# DIGITAL_INPUT.net
KiCad netlist of a schematic drawn in Altium Designer
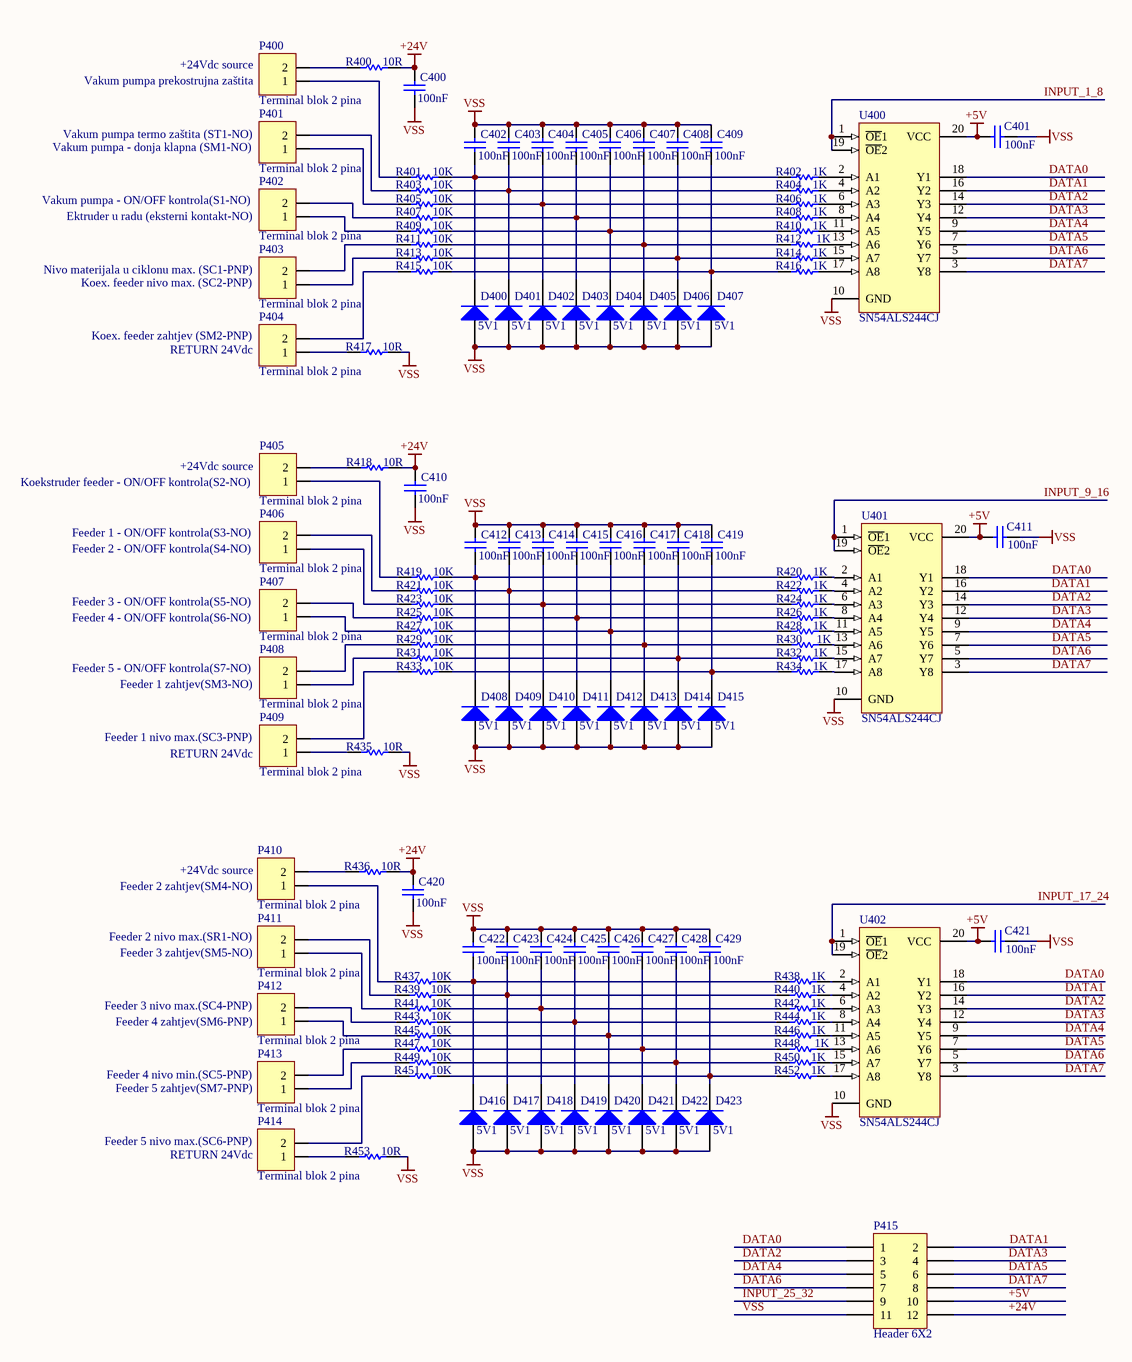
[diagram p0: DIGITAL_INPUT.SchDoc]

(export (version "E")
  (design (tool "Eeschema 10.0.6"))
  (components
    (comp (ref "C400")
      (value "100nF")
      (footprint "1206")
      (description "Ceramic Chip Capacitor - Standard")
      (fields (field (name "PUBLISHER") "Altium Limited"))
      (libsource (lib "KEMET Chip Capacitor") (part "C1206"))
    )
    (comp (ref "C401")
      (value "100nF")
      (footprint "1206")
      (description "Ceramic Chip Capacitor - Standard")
      (fields (field (name "PUBLISHER") "Altium Limited"))
      (libsource (lib "KEMET Chip Capacitor") (part "C1206"))
    )
    (comp (ref "C402")
      (value "100nF")
      (footprint "1206")
      (description "Ceramic Chip Capacitor - Standard")
      (fields (field (name "PUBLISHER") "Altium Limited"))
      (libsource (lib "KEMET Chip Capacitor") (part "C1206"))
    )
    (comp (ref "C403")
      (value "100nF")
      (footprint "1206")
      (description "Ceramic Chip Capacitor - Standard")
      (fields (field (name "PUBLISHER") "Altium Limited"))
      (libsource (lib "KEMET Chip Capacitor") (part "C1206"))
    )
    (comp (ref "C404")
      (value "100nF")
      (footprint "1206")
      (description "Ceramic Chip Capacitor - Standard")
      (fields (field (name "PUBLISHER") "Altium Limited"))
      (libsource (lib "KEMET Chip Capacitor") (part "C1206"))
    )
    (comp (ref "C405")
      (value "100nF")
      (footprint "1206")
      (description "Ceramic Chip Capacitor - Standard")
      (fields (field (name "PUBLISHER") "Altium Limited"))
      (libsource (lib "KEMET Chip Capacitor") (part "C1206"))
    )
    (comp (ref "C406")
      (value "100nF")
      (footprint "1206")
      (description "Ceramic Chip Capacitor - Standard")
      (fields (field (name "PUBLISHER") "Altium Limited"))
      (libsource (lib "KEMET Chip Capacitor") (part "C1206"))
    )
    (comp (ref "C407")
      (value "100nF")
      (footprint "1206")
      (description "Ceramic Chip Capacitor - Standard")
      (fields (field (name "PUBLISHER") "Altium Limited"))
      (libsource (lib "KEMET Chip Capacitor") (part "C1206"))
    )
    (comp (ref "C408")
      (value "100nF")
      (footprint "1206")
      (description "Ceramic Chip Capacitor - Standard")
      (fields (field (name "PUBLISHER") "Altium Limited"))
      (libsource (lib "KEMET Chip Capacitor") (part "C1206"))
    )
    (comp (ref "C409")
      (value "100nF")
      (footprint "1206")
      (description "Ceramic Chip Capacitor - Standard")
      (fields (field (name "PUBLISHER") "Altium Limited"))
      (libsource (lib "KEMET Chip Capacitor") (part "C1206"))
    )
    (comp (ref "C410")
      (value "100nF")
      (footprint "1206")
      (description "Ceramic Chip Capacitor - Standard")
      (fields (field (name "PUBLISHER") "Altium Limited"))
      (libsource (lib "KEMET Chip Capacitor") (part "C1206"))
    )
    (comp (ref "C411")
      (value "100nF")
      (footprint "1206")
      (description "Ceramic Chip Capacitor - Standard")
      (fields (field (name "PUBLISHER") "Altium Limited"))
      (libsource (lib "KEMET Chip Capacitor") (part "C1206"))
    )
    (comp (ref "C412")
      (value "100nF")
      (footprint "1206")
      (description "Ceramic Chip Capacitor - Standard")
      (fields (field (name "PUBLISHER") "Altium Limited"))
      (libsource (lib "KEMET Chip Capacitor") (part "C1206"))
    )
    (comp (ref "C413")
      (value "100nF")
      (footprint "1206")
      (description "Ceramic Chip Capacitor - Standard")
      (fields (field (name "PUBLISHER") "Altium Limited"))
      (libsource (lib "KEMET Chip Capacitor") (part "C1206"))
    )
    (comp (ref "C414")
      (value "100nF")
      (footprint "1206")
      (description "Ceramic Chip Capacitor - Standard")
      (fields (field (name "PUBLISHER") "Altium Limited"))
      (libsource (lib "KEMET Chip Capacitor") (part "C1206"))
    )
    (comp (ref "C415")
      (value "100nF")
      (footprint "1206")
      (description "Ceramic Chip Capacitor - Standard")
      (fields (field (name "PUBLISHER") "Altium Limited"))
      (libsource (lib "KEMET Chip Capacitor") (part "C1206"))
    )
    (comp (ref "C416")
      (value "100nF")
      (footprint "1206")
      (description "Ceramic Chip Capacitor - Standard")
      (fields (field (name "PUBLISHER") "Altium Limited"))
      (libsource (lib "KEMET Chip Capacitor") (part "C1206"))
    )
    (comp (ref "C417")
      (value "100nF")
      (footprint "1206")
      (description "Ceramic Chip Capacitor - Standard")
      (fields (field (name "PUBLISHER") "Altium Limited"))
      (libsource (lib "KEMET Chip Capacitor") (part "C1206"))
    )
    (comp (ref "C418")
      (value "100nF")
      (footprint "1206")
      (description "Ceramic Chip Capacitor - Standard")
      (fields (field (name "PUBLISHER") "Altium Limited"))
      (libsource (lib "KEMET Chip Capacitor") (part "C1206"))
    )
    (comp (ref "C419")
      (value "100nF")
      (footprint "1206")
      (description "Ceramic Chip Capacitor - Standard")
      (fields (field (name "PUBLISHER") "Altium Limited"))
      (libsource (lib "KEMET Chip Capacitor") (part "C1206"))
    )
    (comp (ref "C420")
      (value "100nF")
      (footprint "1206")
      (description "Ceramic Chip Capacitor - Standard")
      (fields (field (name "PUBLISHER") "Altium Limited"))
      (libsource (lib "KEMET Chip Capacitor") (part "C1206"))
    )
    (comp (ref "C421")
      (value "100nF")
      (footprint "1206")
      (description "Ceramic Chip Capacitor - Standard")
      (fields (field (name "PUBLISHER") "Altium Limited"))
      (libsource (lib "KEMET Chip Capacitor") (part "C1206"))
    )
    (comp (ref "C422")
      (value "100nF")
      (footprint "1206")
      (description "Ceramic Chip Capacitor - Standard")
      (fields (field (name "PUBLISHER") "Altium Limited"))
      (libsource (lib "KEMET Chip Capacitor") (part "C1206"))
    )
    (comp (ref "C423")
      (value "100nF")
      (footprint "1206")
      (description "Ceramic Chip Capacitor - Standard")
      (fields (field (name "PUBLISHER") "Altium Limited"))
      (libsource (lib "KEMET Chip Capacitor") (part "C1206"))
    )
    (comp (ref "C424")
      (value "100nF")
      (footprint "1206")
      (description "Ceramic Chip Capacitor - Standard")
      (fields (field (name "PUBLISHER") "Altium Limited"))
      (libsource (lib "KEMET Chip Capacitor") (part "C1206"))
    )
    (comp (ref "C425")
      (value "100nF")
      (footprint "1206")
      (description "Ceramic Chip Capacitor - Standard")
      (fields (field (name "PUBLISHER") "Altium Limited"))
      (libsource (lib "KEMET Chip Capacitor") (part "C1206"))
    )
    (comp (ref "C426")
      (value "100nF")
      (footprint "1206")
      (description "Ceramic Chip Capacitor - Standard")
      (fields (field (name "PUBLISHER") "Altium Limited"))
      (libsource (lib "KEMET Chip Capacitor") (part "C1206"))
    )
    (comp (ref "C427")
      (value "100nF")
      (footprint "1206")
      (description "Ceramic Chip Capacitor - Standard")
      (fields (field (name "PUBLISHER") "Altium Limited"))
      (libsource (lib "KEMET Chip Capacitor") (part "C1206"))
    )
    (comp (ref "C428")
      (value "100nF")
      (footprint "1206")
      (description "Ceramic Chip Capacitor - Standard")
      (fields (field (name "PUBLISHER") "Altium Limited"))
      (libsource (lib "KEMET Chip Capacitor") (part "C1206"))
    )
    (comp (ref "C429")
      (value "100nF")
      (footprint "1206")
      (description "Ceramic Chip Capacitor - Standard")
      (fields (field (name "PUBLISHER") "Altium Limited"))
      (libsource (lib "KEMET Chip Capacitor") (part "C1206"))
    )
    (comp (ref "D400")
      (value "5V1")
      (footprint "SOD80C")
      (description "Voltage Regulator Diode")
      (fields (field (name "PUBLISHER") "Altium Limited"))
      (libsource (lib "Philips Discrete Diode - Switching") (part "BZV85-C5V1"))
    )
    (comp (ref "D401")
      (value "5V1")
      (footprint "SOD80C")
      (description "Voltage Regulator Diode")
      (fields (field (name "PUBLISHER") "Altium Limited"))
      (libsource (lib "Philips Discrete Diode - Switching") (part "BZV85-C5V1"))
    )
    (comp (ref "D402")
      (value "5V1")
      (footprint "SOD80C")
      (description "Voltage Regulator Diode")
      (fields (field (name "PUBLISHER") "Altium Limited"))
      (libsource (lib "Philips Discrete Diode - Switching") (part "BZV85-C5V1"))
    )
    (comp (ref "D403")
      (value "5V1")
      (footprint "SOD80C")
      (description "Voltage Regulator Diode")
      (fields (field (name "PUBLISHER") "Altium Limited"))
      (libsource (lib "Philips Discrete Diode - Switching") (part "BZV85-C5V1"))
    )
    (comp (ref "D404")
      (value "5V1")
      (footprint "SOD80C")
      (description "Voltage Regulator Diode")
      (fields (field (name "PUBLISHER") "Altium Limited"))
      (libsource (lib "Philips Discrete Diode - Switching") (part "BZV85-C5V1"))
    )
    (comp (ref "D405")
      (value "5V1")
      (footprint "SOD80C")
      (description "Voltage Regulator Diode")
      (fields (field (name "PUBLISHER") "Altium Limited"))
      (libsource (lib "Philips Discrete Diode - Switching") (part "BZV85-C5V1"))
    )
    (comp (ref "D406")
      (value "5V1")
      (footprint "SOD80C")
      (description "Voltage Regulator Diode")
      (fields (field (name "PUBLISHER") "Altium Limited"))
      (libsource (lib "Philips Discrete Diode - Switching") (part "BZV85-C5V1"))
    )
    (comp (ref "D407")
      (value "5V1")
      (footprint "SOD80C")
      (description "Voltage Regulator Diode")
      (fields (field (name "PUBLISHER") "Altium Limited"))
      (libsource (lib "Philips Discrete Diode - Switching") (part "BZV85-C5V1"))
    )
    (comp (ref "D408")
      (value "5V1")
      (footprint "SOD80C")
      (description "Voltage Regulator Diode")
      (fields (field (name "PUBLISHER") "Altium Limited"))
      (libsource (lib "Philips Discrete Diode - Switching") (part "BZV85-C5V1"))
    )
    (comp (ref "D409")
      (value "5V1")
      (footprint "SOD80C")
      (description "Voltage Regulator Diode")
      (fields (field (name "PUBLISHER") "Altium Limited"))
      (libsource (lib "Philips Discrete Diode - Switching") (part "BZV85-C5V1"))
    )
    (comp (ref "D410")
      (value "5V1")
      (footprint "SOD80C")
      (description "Voltage Regulator Diode")
      (fields (field (name "PUBLISHER") "Altium Limited"))
      (libsource (lib "Philips Discrete Diode - Switching") (part "BZV85-C5V1"))
    )
    (comp (ref "D411")
      (value "5V1")
      (footprint "SOD80C")
      (description "Voltage Regulator Diode")
      (fields (field (name "PUBLISHER") "Altium Limited"))
      (libsource (lib "Philips Discrete Diode - Switching") (part "BZV85-C5V1"))
    )
    (comp (ref "D412")
      (value "5V1")
      (footprint "SOD80C")
      (description "Voltage Regulator Diode")
      (fields (field (name "PUBLISHER") "Altium Limited"))
      (libsource (lib "Philips Discrete Diode - Switching") (part "BZV85-C5V1"))
    )
    (comp (ref "D413")
      (value "5V1")
      (footprint "SOD80C")
      (description "Voltage Regulator Diode")
      (fields (field (name "PUBLISHER") "Altium Limited"))
      (libsource (lib "Philips Discrete Diode - Switching") (part "BZV85-C5V1"))
    )
    (comp (ref "D414")
      (value "5V1")
      (footprint "SOD80C")
      (description "Voltage Regulator Diode")
      (fields (field (name "PUBLISHER") "Altium Limited"))
      (libsource (lib "Philips Discrete Diode - Switching") (part "BZV85-C5V1"))
    )
    (comp (ref "D415")
      (value "5V1")
      (footprint "SOD80C")
      (description "Voltage Regulator Diode")
      (fields (field (name "PUBLISHER") "Altium Limited"))
      (libsource (lib "Philips Discrete Diode - Switching") (part "BZV85-C5V1"))
    )
    (comp (ref "D416")
      (value "5V1")
      (footprint "SOD80C")
      (description "Voltage Regulator Diode")
      (fields (field (name "PUBLISHER") "Altium Limited"))
      (libsource (lib "Philips Discrete Diode - Switching") (part "BZV85-C5V1"))
    )
    (comp (ref "D417")
      (value "5V1")
      (footprint "SOD80C")
      (description "Voltage Regulator Diode")
      (fields (field (name "PUBLISHER") "Altium Limited"))
      (libsource (lib "Philips Discrete Diode - Switching") (part "BZV85-C5V1"))
    )
    (comp (ref "D418")
      (value "5V1")
      (footprint "SOD80C")
      (description "Voltage Regulator Diode")
      (fields (field (name "PUBLISHER") "Altium Limited"))
      (libsource (lib "Philips Discrete Diode - Switching") (part "BZV85-C5V1"))
    )
    (comp (ref "D419")
      (value "5V1")
      (footprint "SOD80C")
      (description "Voltage Regulator Diode")
      (fields (field (name "PUBLISHER") "Altium Limited"))
      (libsource (lib "Philips Discrete Diode - Switching") (part "BZV85-C5V1"))
    )
    (comp (ref "D420")
      (value "5V1")
      (footprint "SOD80C")
      (description "Voltage Regulator Diode")
      (fields (field (name "PUBLISHER") "Altium Limited"))
      (libsource (lib "Philips Discrete Diode - Switching") (part "BZV85-C5V1"))
    )
    (comp (ref "D421")
      (value "5V1")
      (footprint "SOD80C")
      (description "Voltage Regulator Diode")
      (fields (field (name "PUBLISHER") "Altium Limited"))
      (libsource (lib "Philips Discrete Diode - Switching") (part "BZV85-C5V1"))
    )
    (comp (ref "D422")
      (value "5V1")
      (footprint "SOD80C")
      (description "Voltage Regulator Diode")
      (fields (field (name "PUBLISHER") "Altium Limited"))
      (libsource (lib "Philips Discrete Diode - Switching") (part "BZV85-C5V1"))
    )
    (comp (ref "D423")
      (value "5V1")
      (footprint "SOD80C")
      (description "Voltage Regulator Diode")
      (fields (field (name "PUBLISHER") "Altium Limited"))
      (libsource (lib "Philips Discrete Diode - Switching") (part "BZV85-C5V1"))
    )
    (comp (ref "P400")
      (value "Terminal blok 2 pina")
      (footprint "TERMINAL BLOK 2")
      (description "Terminal blok 2")
      (libsource (lib "") (part "Terminal blok 2 pina_1"))
    )
    (comp (ref "P401")
      (value "Terminal blok 2 pina")
      (footprint "TERMINAL BLOK 2")
      (description "Terminal blok 2")
      (libsource (lib "") (part "Terminal blok 2 pina_1"))
    )
    (comp (ref "P402")
      (value "Terminal blok 2 pina")
      (footprint "TERMINAL BLOK 2")
      (description "Terminal blok 2")
      (libsource (lib "") (part "Terminal blok 2 pina_1"))
    )
    (comp (ref "P403")
      (value "Terminal blok 2 pina")
      (footprint "TERMINAL BLOK 2")
      (description "Terminal blok 2")
      (libsource (lib "TERMINAL_CONNECOR_2") (part "Terminal blok 2 pina"))
    )
    (comp (ref "P404")
      (value "Terminal blok 2 pina")
      (footprint "TERMINAL BLOK 2")
      (description "Terminal blok 2")
      (libsource (lib "TERMINAL_CONNECOR_2") (part "Terminal blok 2 pina"))
    )
    (comp (ref "P405")
      (value "Terminal blok 2 pina")
      (footprint "TERMINAL BLOK 2")
      (description "Terminal blok 2")
      (libsource (lib "TERMINAL_CONNECOR_2") (part "Terminal blok 2 pina"))
    )
    (comp (ref "P406")
      (value "Terminal blok 2 pina")
      (footprint "TERMINAL BLOK 2")
      (description "Terminal blok 2")
      (libsource (lib "TERMINAL_CONNECOR_2") (part "Terminal blok 2 pina"))
    )
    (comp (ref "P407")
      (value "Terminal blok 2 pina")
      (footprint "TERMINAL BLOK 2")
      (description "Terminal blok 2")
      (libsource (lib "TERMINAL_CONNECOR_2") (part "Terminal blok 2 pina"))
    )
    (comp (ref "P408")
      (value "Terminal blok 2 pina")
      (footprint "TERMINAL BLOK 2")
      (description "Terminal blok 2")
      (libsource (lib "TERMINAL_CONNECOR_2") (part "Terminal blok 2 pina"))
    )
    (comp (ref "P409")
      (value "Terminal blok 2 pina")
      (footprint "TERMINAL BLOK 2")
      (description "Terminal blok 2")
      (libsource (lib "TERMINAL_CONNECOR_2") (part "Terminal blok 2 pina"))
    )
    (comp (ref "P410")
      (value "Terminal blok 2 pina")
      (footprint "TERMINAL BLOK 2")
      (description "Terminal blok 2")
      (libsource (lib "") (part "Terminal blok 2 pina_2"))
    )
    (comp (ref "P411")
      (value "Terminal blok 2 pina")
      (footprint "TERMINAL BLOK 2")
      (description "Terminal blok 2")
      (libsource (lib "") (part "Terminal blok 2 pina_2"))
    )
    (comp (ref "P412")
      (value "Terminal blok 2 pina")
      (footprint "TERMINAL BLOK 2")
      (description "Terminal blok 2")
      (libsource (lib "") (part "Terminal blok 2 pina_2"))
    )
    (comp (ref "P413")
      (value "Terminal blok 2 pina")
      (footprint "TERMINAL BLOK 2")
      (description "Terminal blok 2")
      (libsource (lib "") (part "Terminal blok 2 pina_2"))
    )
    (comp (ref "P414")
      (value "Terminal blok 2 pina")
      (footprint "TERMINAL BLOK 2")
      (description "Terminal blok 2")
      (libsource (lib "") (part "Terminal blok 2 pina_2"))
    )
    (comp (ref "P415")
      (value "Header 6X2")
      (footprint "HDR2X6")
      (description "Header, 6-Pin, Dual row")
      (fields (field (name "PUBLISHER") "Altium Limited"))
      (libsource (lib "Miscellaneous Connectors") (part "Header 6X2"))
    )
    (comp (ref "R400")
      (value "10R")
      (footprint "ERA-0805")
      (fields (field (name "PUBLISHER") "Altium Limited"))
      (libsource (lib "Panasonic Resistor") (part "ERA6Y"))
    )
    (comp (ref "R401")
      (value "10K")
      (footprint "ERA-0805")
      (fields (field (name "PUBLISHER") "Altium Limited"))
      (libsource (lib "Panasonic Resistor") (part "ERA6Y"))
    )
    (comp (ref "R402")
      (value "1K")
      (footprint "ERA-0805")
      (fields (field (name "PUBLISHER") "Altium Limited"))
      (libsource (lib "Panasonic Resistor") (part "ERA6Y"))
    )
    (comp (ref "R403")
      (value "10K")
      (footprint "ERA-0805")
      (fields (field (name "PUBLISHER") "Altium Limited"))
      (libsource (lib "Panasonic Resistor") (part "ERA6Y"))
    )
    (comp (ref "R404")
      (value "1K")
      (footprint "ERA-0805")
      (fields (field (name "PUBLISHER") "Altium Limited"))
      (libsource (lib "Panasonic Resistor") (part "ERA6Y"))
    )
    (comp (ref "R405")
      (value "10K")
      (footprint "ERA-0805")
      (fields (field (name "PUBLISHER") "Altium Limited"))
      (libsource (lib "Panasonic Resistor") (part "ERA6Y"))
    )
    (comp (ref "R406")
      (value "1K")
      (footprint "ERA-0805")
      (fields (field (name "PUBLISHER") "Altium Limited"))
      (libsource (lib "Panasonic Resistor") (part "ERA6Y"))
    )
    (comp (ref "R407")
      (value "10K")
      (footprint "ERA-0805")
      (fields (field (name "PUBLISHER") "Altium Limited"))
      (libsource (lib "Panasonic Resistor") (part "ERA6Y"))
    )
    (comp (ref "R408")
      (value "1K")
      (footprint "ERA-0805")
      (fields (field (name "PUBLISHER") "Altium Limited"))
      (libsource (lib "Panasonic Resistor") (part "ERA6Y"))
    )
    (comp (ref "R409")
      (value "10K")
      (footprint "ERA-0805")
      (fields (field (name "PUBLISHER") "Altium Limited"))
      (libsource (lib "Panasonic Resistor") (part "ERA6Y"))
    )
    (comp (ref "R410")
      (value "1K")
      (footprint "ERA-0805")
      (fields (field (name "PUBLISHER") "Altium Limited"))
      (libsource (lib "Panasonic Resistor") (part "ERA6Y"))
    )
    (comp (ref "R411")
      (value "10K")
      (footprint "ERA-0805")
      (fields (field (name "PUBLISHER") "Altium Limited"))
      (libsource (lib "Panasonic Resistor") (part "ERA6Y"))
    )
    (comp (ref "R412")
      (value "1K")
      (footprint "ERA-0805")
      (fields (field (name "PUBLISHER") "Altium Limited"))
      (libsource (lib "Panasonic Resistor") (part "ERA6Y"))
    )
    (comp (ref "R413")
      (value "10K")
      (footprint "ERA-0805")
      (fields (field (name "PUBLISHER") "Altium Limited"))
      (libsource (lib "Panasonic Resistor") (part "ERA6Y"))
    )
    (comp (ref "R414")
      (value "1K")
      (footprint "ERA-0805")
      (fields (field (name "PUBLISHER") "Altium Limited"))
      (libsource (lib "Panasonic Resistor") (part "ERA6Y"))
    )
    (comp (ref "R415")
      (value "10K")
      (footprint "ERA-0805")
      (fields (field (name "PUBLISHER") "Altium Limited"))
      (libsource (lib "Panasonic Resistor") (part "ERA6Y"))
    )
    (comp (ref "R416")
      (value "1K")
      (footprint "ERA-0805")
      (fields (field (name "PUBLISHER") "Altium Limited"))
      (libsource (lib "Panasonic Resistor") (part "ERA6Y"))
    )
    (comp (ref "R417")
      (value "10R")
      (footprint "ERA-0805")
      (fields (field (name "PUBLISHER") "Altium Limited"))
      (libsource (lib "Panasonic Resistor") (part "ERA6Y"))
    )
    (comp (ref "R418")
      (value "10R")
      (footprint "ERA-0805")
      (fields (field (name "PUBLISHER") "Altium Limited"))
      (libsource (lib "Panasonic Resistor") (part "ERA6Y"))
    )
    (comp (ref "R419")
      (value "10K")
      (footprint "ERA-0805")
      (fields (field (name "PUBLISHER") "Altium Limited"))
      (libsource (lib "Panasonic Resistor") (part "ERA6Y"))
    )
    (comp (ref "R420")
      (value "1K")
      (footprint "ERA-0805")
      (fields (field (name "PUBLISHER") "Altium Limited"))
      (libsource (lib "Panasonic Resistor") (part "ERA6Y"))
    )
    (comp (ref "R421")
      (value "10K")
      (footprint "ERA-0805")
      (fields (field (name "PUBLISHER") "Altium Limited"))
      (libsource (lib "Panasonic Resistor") (part "ERA6Y"))
    )
    (comp (ref "R422")
      (value "1K")
      (footprint "ERA-0805")
      (fields (field (name "PUBLISHER") "Altium Limited"))
      (libsource (lib "Panasonic Resistor") (part "ERA6Y"))
    )
    (comp (ref "R423")
      (value "10K")
      (footprint "ERA-0805")
      (fields (field (name "PUBLISHER") "Altium Limited"))
      (libsource (lib "Panasonic Resistor") (part "ERA6Y"))
    )
    (comp (ref "R424")
      (value "1K")
      (footprint "ERA-0805")
      (fields (field (name "PUBLISHER") "Altium Limited"))
      (libsource (lib "Panasonic Resistor") (part "ERA6Y"))
    )
    (comp (ref "R425")
      (value "10K")
      (footprint "ERA-0805")
      (fields (field (name "PUBLISHER") "Altium Limited"))
      (libsource (lib "Panasonic Resistor") (part "ERA6Y"))
    )
    (comp (ref "R426")
      (value "1K")
      (footprint "ERA-0805")
      (fields (field (name "PUBLISHER") "Altium Limited"))
      (libsource (lib "Panasonic Resistor") (part "ERA6Y"))
    )
    (comp (ref "R427")
      (value "10K")
      (footprint "ERA-0805")
      (fields (field (name "PUBLISHER") "Altium Limited"))
      (libsource (lib "Panasonic Resistor") (part "ERA6Y"))
    )
    (comp (ref "R428")
      (value "1K")
      (footprint "ERA-0805")
      (fields (field (name "PUBLISHER") "Altium Limited"))
      (libsource (lib "Panasonic Resistor") (part "ERA6Y"))
    )
    (comp (ref "R429")
      (value "10K")
      (footprint "ERA-0805")
      (fields (field (name "PUBLISHER") "Altium Limited"))
      (libsource (lib "Panasonic Resistor") (part "ERA6Y"))
    )
    (comp (ref "R430")
      (value "1K")
      (footprint "ERA-0805")
      (fields (field (name "PUBLISHER") "Altium Limited"))
      (libsource (lib "Panasonic Resistor") (part "ERA6Y"))
    )
    (comp (ref "R431")
      (value "10K")
      (footprint "ERA-0805")
      (fields (field (name "PUBLISHER") "Altium Limited"))
      (libsource (lib "Panasonic Resistor") (part "ERA6Y"))
    )
    (comp (ref "R432")
      (value "1K")
      (footprint "ERA-0805")
      (fields (field (name "PUBLISHER") "Altium Limited"))
      (libsource (lib "Panasonic Resistor") (part "ERA6Y"))
    )
    (comp (ref "R433")
      (value "10K")
      (footprint "ERA-0805")
      (fields (field (name "PUBLISHER") "Altium Limited"))
      (libsource (lib "Panasonic Resistor") (part "ERA6Y"))
    )
    (comp (ref "R434")
      (value "1K")
      (footprint "ERA-0805")
      (fields (field (name "PUBLISHER") "Altium Limited"))
      (libsource (lib "Panasonic Resistor") (part "ERA6Y"))
    )
    (comp (ref "R435")
      (value "10R")
      (footprint "ERA-0805")
      (fields (field (name "PUBLISHER") "Altium Limited"))
      (libsource (lib "Panasonic Resistor") (part "ERA6Y"))
    )
    (comp (ref "R436")
      (value "10R")
      (footprint "ERA-0805")
      (fields (field (name "PUBLISHER") "Altium Limited"))
      (libsource (lib "Panasonic Resistor") (part "ERA6Y"))
    )
    (comp (ref "R437")
      (value "10K")
      (footprint "ERA-0805")
      (fields (field (name "PUBLISHER") "Altium Limited"))
      (libsource (lib "Panasonic Resistor") (part "ERA6Y"))
    )
    (comp (ref "R438")
      (value "1K")
      (footprint "ERA-0805")
      (fields (field (name "PUBLISHER") "Altium Limited"))
      (libsource (lib "Panasonic Resistor") (part "ERA6Y"))
    )
    (comp (ref "R439")
      (value "10K")
      (footprint "ERA-0805")
      (fields (field (name "PUBLISHER") "Altium Limited"))
      (libsource (lib "Panasonic Resistor") (part "ERA6Y"))
    )
    (comp (ref "R440")
      (value "1K")
      (footprint "ERA-0805")
      (fields (field (name "PUBLISHER") "Altium Limited"))
      (libsource (lib "Panasonic Resistor") (part "ERA6Y"))
    )
    (comp (ref "R441")
      (value "10K")
      (footprint "ERA-0805")
      (fields (field (name "PUBLISHER") "Altium Limited"))
      (libsource (lib "Panasonic Resistor") (part "ERA6Y"))
    )
    (comp (ref "R442")
      (value "1K")
      (footprint "ERA-0805")
      (fields (field (name "PUBLISHER") "Altium Limited"))
      (libsource (lib "Panasonic Resistor") (part "ERA6Y"))
    )
    (comp (ref "R443")
      (value "10K")
      (footprint "ERA-0805")
      (fields (field (name "PUBLISHER") "Altium Limited"))
      (libsource (lib "Panasonic Resistor") (part "ERA6Y"))
    )
    (comp (ref "R444")
      (value "1K")
      (footprint "ERA-0805")
      (fields (field (name "PUBLISHER") "Altium Limited"))
      (libsource (lib "Panasonic Resistor") (part "ERA6Y"))
    )
    (comp (ref "R445")
      (value "10K")
      (footprint "ERA-0805")
      (fields (field (name "PUBLISHER") "Altium Limited"))
      (libsource (lib "Panasonic Resistor") (part "ERA6Y"))
    )
    (comp (ref "R446")
      (value "1K")
      (footprint "ERA-0805")
      (fields (field (name "PUBLISHER") "Altium Limited"))
      (libsource (lib "Panasonic Resistor") (part "ERA6Y"))
    )
    (comp (ref "R447")
      (value "10K")
      (footprint "ERA-0805")
      (fields (field (name "PUBLISHER") "Altium Limited"))
      (libsource (lib "Panasonic Resistor") (part "ERA6Y"))
    )
    (comp (ref "R448")
      (value "1K")
      (footprint "ERA-0805")
      (fields (field (name "PUBLISHER") "Altium Limited"))
      (libsource (lib "Panasonic Resistor") (part "ERA6Y"))
    )
    (comp (ref "R449")
      (value "10K")
      (footprint "ERA-0805")
      (fields (field (name "PUBLISHER") "Altium Limited"))
      (libsource (lib "Panasonic Resistor") (part "ERA6Y"))
    )
    (comp (ref "R450")
      (value "1K")
      (footprint "ERA-0805")
      (fields (field (name "PUBLISHER") "Altium Limited"))
      (libsource (lib "Panasonic Resistor") (part "ERA6Y"))
    )
    (comp (ref "R451")
      (value "10K")
      (footprint "ERA-0805")
      (fields (field (name "PUBLISHER") "Altium Limited"))
      (libsource (lib "Panasonic Resistor") (part "ERA6Y"))
    )
    (comp (ref "R452")
      (value "1K")
      (footprint "ERA-0805")
      (fields (field (name "PUBLISHER") "Altium Limited"))
      (libsource (lib "Panasonic Resistor") (part "ERA6Y"))
    )
    (comp (ref "R453")
      (value "10R")
      (footprint "ERA-0805")
      (fields (field (name "PUBLISHER") "Altium Limited"))
      (libsource (lib "Panasonic Resistor") (part "ERA6Y"))
    )
    (comp (ref "U400")
      (value "SN54ALS244CJ")
      (footprint "J020")
      (description "Octal Buffer/Driver with 3-State Outputs")
      (fields (field (name "PUBLISHER") "Altium Limited"))
      (libsource (lib "TI Logic Buffer Line Driver") (part "SN54ALS244CJ"))
    )
    (comp (ref "U401")
      (value "SN54ALS244CJ")
      (footprint "J020")
      (description "Octal Buffer/Driver with 3-State Outputs")
      (fields (field (name "PUBLISHER") "Altium Limited"))
      (libsource (lib "TI Logic Buffer Line Driver") (part "SN54ALS244CJ"))
    )
    (comp (ref "U402")
      (value "SN54ALS244CJ")
      (footprint "J020")
      (description "Octal Buffer/Driver with 3-State Outputs")
      (fields (field (name "PUBLISHER") "Altium Limited"))
      (libsource (lib "TI Logic Buffer Line Driver") (part "SN54ALS244CJ"))
    )
  )
  (nets
    (net (code "1") (name "+5V") (class "Default")
      (node (ref "C401") (pin "1") (pinfunction "1_1") (pintype "passive"))
      (node (ref "C411") (pin "1") (pinfunction "1_1") (pintype "passive"))
      (node (ref "C421") (pin "1") (pinfunction "1_1") (pintype "passive"))
      (node (ref "P415") (pin "10") (pinfunction "10_10") (pintype "passive"))
      (node (ref "U400") (pin "20") (pinfunction "VCC_20") (pintype "power_in"))
      (node (ref "U401") (pin "20") (pinfunction "VCC_20") (pintype "power_in"))
      (node (ref "U402") (pin "20") (pinfunction "VCC_20") (pintype "power_in"))
    )
    (net (code "2") (name "+24V") (class "Default")
      (node (ref "C400") (pin "2") (pinfunction "2_2") (pintype "passive"))
      (node (ref "C410") (pin "2") (pinfunction "2_2") (pintype "passive"))
      (node (ref "C420") (pin "2") (pinfunction "2_2") (pintype "passive"))
      (node (ref "P415") (pin "12") (pinfunction "12_12") (pintype "passive"))
      (node (ref "R400") (pin "2") (pinfunction "2_2") (pintype "passive"))
      (node (ref "R418") (pin "2") (pinfunction "2_2") (pintype "passive"))
      (node (ref "R436") (pin "2") (pinfunction "2_2") (pintype "passive"))
    )
    (net (code "3") (name "/DATA0") (class "Default")
      (node (ref "P415") (pin "1") (pinfunction "1_1") (pintype "passive"))
      (node (ref "U400") (pin "18") (pinfunction "Y1_18") (pintype "tri_state"))
      (node (ref "U401") (pin "18") (pinfunction "Y1_18") (pintype "tri_state"))
      (node (ref "U402") (pin "18") (pinfunction "Y1_18") (pintype "tri_state"))
    )
    (net (code "4") (name "/DATA1") (class "Default")
      (node (ref "P415") (pin "2") (pinfunction "2_2") (pintype "passive"))
      (node (ref "U400") (pin "16") (pinfunction "Y2_16") (pintype "tri_state"))
      (node (ref "U401") (pin "16") (pinfunction "Y2_16") (pintype "tri_state"))
      (node (ref "U402") (pin "16") (pinfunction "Y2_16") (pintype "tri_state"))
    )
    (net (code "5") (name "/DATA2") (class "Default")
      (node (ref "P415") (pin "3") (pinfunction "3_3") (pintype "passive"))
      (node (ref "U400") (pin "14") (pinfunction "Y3_14") (pintype "tri_state"))
      (node (ref "U401") (pin "14") (pinfunction "Y3_14") (pintype "tri_state"))
      (node (ref "U402") (pin "14") (pinfunction "Y3_14") (pintype "tri_state"))
    )
    (net (code "6") (name "/DATA3") (class "Default")
      (node (ref "P415") (pin "4") (pinfunction "4_4") (pintype "passive"))
      (node (ref "U400") (pin "12") (pinfunction "Y4_12") (pintype "tri_state"))
      (node (ref "U401") (pin "12") (pinfunction "Y4_12") (pintype "tri_state"))
      (node (ref "U402") (pin "12") (pinfunction "Y4_12") (pintype "tri_state"))
    )
    (net (code "7") (name "/DATA4") (class "Default")
      (node (ref "P415") (pin "5") (pinfunction "5_5") (pintype "passive"))
      (node (ref "U400") (pin "9") (pinfunction "Y5_9") (pintype "tri_state"))
      (node (ref "U401") (pin "9") (pinfunction "Y5_9") (pintype "tri_state"))
      (node (ref "U402") (pin "9") (pinfunction "Y5_9") (pintype "tri_state"))
    )
    (net (code "8") (name "/DATA5") (class "Default")
      (node (ref "P415") (pin "6") (pinfunction "6_6") (pintype "passive"))
      (node (ref "U400") (pin "7") (pinfunction "Y6_7") (pintype "tri_state"))
      (node (ref "U401") (pin "7") (pinfunction "Y6_7") (pintype "tri_state"))
      (node (ref "U402") (pin "7") (pinfunction "Y6_7") (pintype "tri_state"))
    )
    (net (code "9") (name "/DATA6") (class "Default")
      (node (ref "P415") (pin "7") (pinfunction "7_7") (pintype "passive"))
      (node (ref "U400") (pin "5") (pinfunction "Y7_5") (pintype "tri_state"))
      (node (ref "U401") (pin "5") (pinfunction "Y7_5") (pintype "tri_state"))
      (node (ref "U402") (pin "5") (pinfunction "Y7_5") (pintype "tri_state"))
    )
    (net (code "10") (name "/DATA7") (class "Default")
      (node (ref "P415") (pin "8") (pinfunction "8_8") (pintype "passive"))
      (node (ref "U400") (pin "3") (pinfunction "Y8_3") (pintype "tri_state"))
      (node (ref "U401") (pin "3") (pinfunction "Y8_3") (pintype "tri_state"))
      (node (ref "U402") (pin "3") (pinfunction "Y8_3") (pintype "tri_state"))
    )
    (net (code "11") (name "/INPUT_1_8") (class "Default")
      (node (ref "U400") (pin "1") (pinfunction "~{OE}1_1") (pintype "input"))
      (node (ref "U400") (pin "19") (pinfunction "~{OE}2_19") (pintype "input"))
    )
    (net (code "12") (name "/INPUT_9_16") (class "Default")
      (node (ref "U401") (pin "1") (pinfunction "~{OE}1_1") (pintype "input"))
      (node (ref "U401") (pin "19") (pinfunction "~{OE}2_19") (pintype "input"))
    )
    (net (code "13") (name "/INPUT_17_24") (class "Default")
      (node (ref "U402") (pin "1") (pinfunction "~{OE}1_1") (pintype "input"))
      (node (ref "U402") (pin "19") (pinfunction "~{OE}2_19") (pintype "input"))
    )
    (net (code "14") (name "/INPUT_25_32") (class "Default")
      (node (ref "P415") (pin "9") (pinfunction "9_9") (pintype "passive"))
    )
    (net (code "15") (name "Net-(D400-K)") (class "Default")
      (node (ref "C402") (pin "1") (pinfunction "1_1") (pintype "passive"))
      (node (ref "D400") (pin "2") (pinfunction "K_2") (pintype "passive"))
      (node (ref "R401") (pin "2") (pinfunction "2_2") (pintype "passive"))
      (node (ref "R402") (pin "1") (pinfunction "1_1") (pintype "passive"))
    )
    (net (code "16") (name "Net-(D401-K)") (class "Default")
      (node (ref "C403") (pin "1") (pinfunction "1_1") (pintype "passive"))
      (node (ref "D401") (pin "2") (pinfunction "K_2") (pintype "passive"))
      (node (ref "R403") (pin "2") (pinfunction "2_2") (pintype "passive"))
      (node (ref "R404") (pin "1") (pinfunction "1_1") (pintype "passive"))
    )
    (net (code "17") (name "Net-(D402-K)") (class "Default")
      (node (ref "C404") (pin "1") (pinfunction "1_1") (pintype "passive"))
      (node (ref "D402") (pin "2") (pinfunction "K_2") (pintype "passive"))
      (node (ref "R405") (pin "2") (pinfunction "2_2") (pintype "passive"))
      (node (ref "R406") (pin "1") (pinfunction "1_1") (pintype "passive"))
    )
    (net (code "18") (name "Net-(D403-K)") (class "Default")
      (node (ref "C405") (pin "1") (pinfunction "1_1") (pintype "passive"))
      (node (ref "D403") (pin "2") (pinfunction "K_2") (pintype "passive"))
      (node (ref "R407") (pin "2") (pinfunction "2_2") (pintype "passive"))
      (node (ref "R408") (pin "1") (pinfunction "1_1") (pintype "passive"))
    )
    (net (code "19") (name "Net-(D404-K)") (class "Default")
      (node (ref "C406") (pin "1") (pinfunction "1_1") (pintype "passive"))
      (node (ref "D404") (pin "2") (pinfunction "K_2") (pintype "passive"))
      (node (ref "R409") (pin "2") (pinfunction "2_2") (pintype "passive"))
      (node (ref "R410") (pin "1") (pinfunction "1_1") (pintype "passive"))
    )
    (net (code "20") (name "Net-(D405-K)") (class "Default")
      (node (ref "C407") (pin "1") (pinfunction "1_1") (pintype "passive"))
      (node (ref "D405") (pin "2") (pinfunction "K_2") (pintype "passive"))
      (node (ref "R411") (pin "2") (pinfunction "2_2") (pintype "passive"))
      (node (ref "R412") (pin "1") (pinfunction "1_1") (pintype "passive"))
    )
    (net (code "21") (name "Net-(D406-K)") (class "Default")
      (node (ref "C408") (pin "1") (pinfunction "1_1") (pintype "passive"))
      (node (ref "D406") (pin "2") (pinfunction "K_2") (pintype "passive"))
      (node (ref "R413") (pin "2") (pinfunction "2_2") (pintype "passive"))
      (node (ref "R414") (pin "1") (pinfunction "1_1") (pintype "passive"))
    )
    (net (code "22") (name "Net-(D407-K)") (class "Default")
      (node (ref "C409") (pin "1") (pinfunction "1_1") (pintype "passive"))
      (node (ref "D407") (pin "2") (pinfunction "K_2") (pintype "passive"))
      (node (ref "R415") (pin "2") (pinfunction "2_2") (pintype "passive"))
      (node (ref "R416") (pin "1") (pinfunction "1_1") (pintype "passive"))
    )
    (net (code "23") (name "Net-(D408-K)") (class "Default")
      (node (ref "C412") (pin "1") (pinfunction "1_1") (pintype "passive"))
      (node (ref "D408") (pin "2") (pinfunction "K_2") (pintype "passive"))
      (node (ref "R419") (pin "2") (pinfunction "2_2") (pintype "passive"))
      (node (ref "R420") (pin "1") (pinfunction "1_1") (pintype "passive"))
    )
    (net (code "24") (name "Net-(D409-K)") (class "Default")
      (node (ref "C413") (pin "1") (pinfunction "1_1") (pintype "passive"))
      (node (ref "D409") (pin "2") (pinfunction "K_2") (pintype "passive"))
      (node (ref "R421") (pin "2") (pinfunction "2_2") (pintype "passive"))
      (node (ref "R422") (pin "1") (pinfunction "1_1") (pintype "passive"))
    )
    (net (code "25") (name "Net-(D410-K)") (class "Default")
      (node (ref "C414") (pin "1") (pinfunction "1_1") (pintype "passive"))
      (node (ref "D410") (pin "2") (pinfunction "K_2") (pintype "passive"))
      (node (ref "R423") (pin "2") (pinfunction "2_2") (pintype "passive"))
      (node (ref "R424") (pin "1") (pinfunction "1_1") (pintype "passive"))
    )
    (net (code "26") (name "Net-(D411-K)") (class "Default")
      (node (ref "C415") (pin "1") (pinfunction "1_1") (pintype "passive"))
      (node (ref "D411") (pin "2") (pinfunction "K_2") (pintype "passive"))
      (node (ref "R425") (pin "2") (pinfunction "2_2") (pintype "passive"))
      (node (ref "R426") (pin "1") (pinfunction "1_1") (pintype "passive"))
    )
    (net (code "27") (name "Net-(D412-K)") (class "Default")
      (node (ref "C416") (pin "1") (pinfunction "1_1") (pintype "passive"))
      (node (ref "D412") (pin "2") (pinfunction "K_2") (pintype "passive"))
      (node (ref "R427") (pin "2") (pinfunction "2_2") (pintype "passive"))
      (node (ref "R428") (pin "1") (pinfunction "1_1") (pintype "passive"))
    )
    (net (code "28") (name "Net-(D413-K)") (class "Default")
      (node (ref "C417") (pin "1") (pinfunction "1_1") (pintype "passive"))
      (node (ref "D413") (pin "2") (pinfunction "K_2") (pintype "passive"))
      (node (ref "R429") (pin "2") (pinfunction "2_2") (pintype "passive"))
      (node (ref "R430") (pin "1") (pinfunction "1_1") (pintype "passive"))
    )
    (net (code "29") (name "Net-(D414-K)") (class "Default")
      (node (ref "C418") (pin "1") (pinfunction "1_1") (pintype "passive"))
      (node (ref "D414") (pin "2") (pinfunction "K_2") (pintype "passive"))
      (node (ref "R431") (pin "2") (pinfunction "2_2") (pintype "passive"))
      (node (ref "R432") (pin "1") (pinfunction "1_1") (pintype "passive"))
    )
    (net (code "30") (name "Net-(D415-K)") (class "Default")
      (node (ref "C419") (pin "1") (pinfunction "1_1") (pintype "passive"))
      (node (ref "D415") (pin "2") (pinfunction "K_2") (pintype "passive"))
      (node (ref "R433") (pin "2") (pinfunction "2_2") (pintype "passive"))
      (node (ref "R434") (pin "1") (pinfunction "1_1") (pintype "passive"))
    )
    (net (code "31") (name "Net-(D416-K)") (class "Default")
      (node (ref "C422") (pin "1") (pinfunction "1_1") (pintype "passive"))
      (node (ref "D416") (pin "2") (pinfunction "K_2") (pintype "passive"))
      (node (ref "R437") (pin "2") (pinfunction "2_2") (pintype "passive"))
      (node (ref "R438") (pin "1") (pinfunction "1_1") (pintype "passive"))
    )
    (net (code "32") (name "Net-(D417-K)") (class "Default")
      (node (ref "C423") (pin "1") (pinfunction "1_1") (pintype "passive"))
      (node (ref "D417") (pin "2") (pinfunction "K_2") (pintype "passive"))
      (node (ref "R439") (pin "2") (pinfunction "2_2") (pintype "passive"))
      (node (ref "R440") (pin "1") (pinfunction "1_1") (pintype "passive"))
    )
    (net (code "33") (name "Net-(D418-K)") (class "Default")
      (node (ref "C424") (pin "1") (pinfunction "1_1") (pintype "passive"))
      (node (ref "D418") (pin "2") (pinfunction "K_2") (pintype "passive"))
      (node (ref "R441") (pin "2") (pinfunction "2_2") (pintype "passive"))
      (node (ref "R442") (pin "1") (pinfunction "1_1") (pintype "passive"))
    )
    (net (code "34") (name "Net-(D419-K)") (class "Default")
      (node (ref "C425") (pin "1") (pinfunction "1_1") (pintype "passive"))
      (node (ref "D419") (pin "2") (pinfunction "K_2") (pintype "passive"))
      (node (ref "R443") (pin "2") (pinfunction "2_2") (pintype "passive"))
      (node (ref "R444") (pin "1") (pinfunction "1_1") (pintype "passive"))
    )
    (net (code "35") (name "Net-(D420-K)") (class "Default")
      (node (ref "C426") (pin "1") (pinfunction "1_1") (pintype "passive"))
      (node (ref "D420") (pin "2") (pinfunction "K_2") (pintype "passive"))
      (node (ref "R445") (pin "2") (pinfunction "2_2") (pintype "passive"))
      (node (ref "R446") (pin "1") (pinfunction "1_1") (pintype "passive"))
    )
    (net (code "36") (name "Net-(D421-K)") (class "Default")
      (node (ref "C427") (pin "1") (pinfunction "1_1") (pintype "passive"))
      (node (ref "D421") (pin "2") (pinfunction "K_2") (pintype "passive"))
      (node (ref "R447") (pin "2") (pinfunction "2_2") (pintype "passive"))
      (node (ref "R448") (pin "1") (pinfunction "1_1") (pintype "passive"))
    )
    (net (code "37") (name "Net-(D422-K)") (class "Default")
      (node (ref "C428") (pin "1") (pinfunction "1_1") (pintype "passive"))
      (node (ref "D422") (pin "2") (pinfunction "K_2") (pintype "passive"))
      (node (ref "R449") (pin "2") (pinfunction "2_2") (pintype "passive"))
      (node (ref "R450") (pin "1") (pinfunction "1_1") (pintype "passive"))
    )
    (net (code "38") (name "Net-(D423-K)") (class "Default")
      (node (ref "C429") (pin "1") (pinfunction "1_1") (pintype "passive"))
      (node (ref "D423") (pin "2") (pinfunction "K_2") (pintype "passive"))
      (node (ref "R451") (pin "2") (pinfunction "2_2") (pintype "passive"))
      (node (ref "R452") (pin "1") (pinfunction "1_1") (pintype "passive"))
    )
    (net (code "39") (name "Net-(P400-Pad1)") (class "Default")
      (node (ref "P400") (pin "1") (pinfunction "1_1") (pintype "passive"))
      (node (ref "R401") (pin "1") (pinfunction "1_1") (pintype "passive"))
    )
    (net (code "40") (name "Net-(P400-Pad2)") (class "Default")
      (node (ref "P400") (pin "2") (pinfunction "2_2") (pintype "passive"))
      (node (ref "R400") (pin "1") (pinfunction "1_1") (pintype "passive"))
    )
    (net (code "41") (name "Net-(P401-Pad1)") (class "Default")
      (node (ref "P401") (pin "1") (pinfunction "1_1") (pintype "passive"))
      (node (ref "R405") (pin "1") (pinfunction "1_1") (pintype "passive"))
    )
    (net (code "42") (name "Net-(P401-Pad2)") (class "Default")
      (node (ref "P401") (pin "2") (pinfunction "2_2") (pintype "passive"))
      (node (ref "R403") (pin "1") (pinfunction "1_1") (pintype "passive"))
    )
    (net (code "43") (name "Net-(P402-Pad1)") (class "Default")
      (node (ref "P402") (pin "1") (pinfunction "1_1") (pintype "passive"))
      (node (ref "R409") (pin "1") (pinfunction "1_1") (pintype "passive"))
    )
    (net (code "44") (name "Net-(P402-Pad2)") (class "Default")
      (node (ref "P402") (pin "2") (pinfunction "2_2") (pintype "passive"))
      (node (ref "R407") (pin "1") (pinfunction "1_1") (pintype "passive"))
    )
    (net (code "45") (name "Net-(P403-Pad1)") (class "Default")
      (node (ref "P403") (pin "1") (pinfunction "1_1") (pintype "passive"))
      (node (ref "R413") (pin "1") (pinfunction "1_1") (pintype "passive"))
    )
    (net (code "46") (name "Net-(P403-Pad2)") (class "Default")
      (node (ref "P403") (pin "2") (pinfunction "2_2") (pintype "passive"))
      (node (ref "R411") (pin "1") (pinfunction "1_1") (pintype "passive"))
    )
    (net (code "47") (name "Net-(P404-Pad1)") (class "Default")
      (node (ref "P404") (pin "1") (pinfunction "1_1") (pintype "passive"))
      (node (ref "R417") (pin "1") (pinfunction "1_1") (pintype "passive"))
    )
    (net (code "48") (name "Net-(P404-Pad2)") (class "Default")
      (node (ref "P404") (pin "2") (pinfunction "2_2") (pintype "passive"))
      (node (ref "R415") (pin "1") (pinfunction "1_1") (pintype "passive"))
    )
    (net (code "49") (name "Net-(P405-Pad1)") (class "Default")
      (node (ref "P405") (pin "1") (pinfunction "1_1") (pintype "passive"))
      (node (ref "R419") (pin "1") (pinfunction "1_1") (pintype "passive"))
    )
    (net (code "50") (name "Net-(P405-Pad2)") (class "Default")
      (node (ref "P405") (pin "2") (pinfunction "2_2") (pintype "passive"))
      (node (ref "R418") (pin "1") (pinfunction "1_1") (pintype "passive"))
    )
    (net (code "51") (name "Net-(P406-Pad1)") (class "Default")
      (node (ref "P406") (pin "1") (pinfunction "1_1") (pintype "passive"))
      (node (ref "R423") (pin "1") (pinfunction "1_1") (pintype "passive"))
    )
    (net (code "52") (name "Net-(P406-Pad2)") (class "Default")
      (node (ref "P406") (pin "2") (pinfunction "2_2") (pintype "passive"))
      (node (ref "R421") (pin "1") (pinfunction "1_1") (pintype "passive"))
    )
    (net (code "53") (name "Net-(P407-Pad1)") (class "Default")
      (node (ref "P407") (pin "1") (pinfunction "1_1") (pintype "passive"))
      (node (ref "R427") (pin "1") (pinfunction "1_1") (pintype "passive"))
    )
    (net (code "54") (name "Net-(P407-Pad2)") (class "Default")
      (node (ref "P407") (pin "2") (pinfunction "2_2") (pintype "passive"))
      (node (ref "R425") (pin "1") (pinfunction "1_1") (pintype "passive"))
    )
    (net (code "55") (name "Net-(P408-Pad1)") (class "Default")
      (node (ref "P408") (pin "1") (pinfunction "1_1") (pintype "passive"))
      (node (ref "R431") (pin "1") (pinfunction "1_1") (pintype "passive"))
    )
    (net (code "56") (name "Net-(P408-Pad2)") (class "Default")
      (node (ref "P408") (pin "2") (pinfunction "2_2") (pintype "passive"))
      (node (ref "R429") (pin "1") (pinfunction "1_1") (pintype "passive"))
    )
    (net (code "57") (name "Net-(P409-Pad1)") (class "Default")
      (node (ref "P409") (pin "1") (pinfunction "1_1") (pintype "passive"))
      (node (ref "R435") (pin "1") (pinfunction "1_1") (pintype "passive"))
    )
    (net (code "58") (name "Net-(P409-Pad2)") (class "Default")
      (node (ref "P409") (pin "2") (pinfunction "2_2") (pintype "passive"))
      (node (ref "R433") (pin "1") (pinfunction "1_1") (pintype "passive"))
    )
    (net (code "59") (name "Net-(P410-Pad1)") (class "Default")
      (node (ref "P410") (pin "1") (pinfunction "1_1") (pintype "passive"))
      (node (ref "R437") (pin "1") (pinfunction "1_1") (pintype "passive"))
    )
    (net (code "60") (name "Net-(P410-Pad2)") (class "Default")
      (node (ref "P410") (pin "2") (pinfunction "2_2") (pintype "passive"))
      (node (ref "R436") (pin "1") (pinfunction "1_1") (pintype "passive"))
    )
    (net (code "61") (name "Net-(P411-Pad1)") (class "Default")
      (node (ref "P411") (pin "1") (pinfunction "1_1") (pintype "passive"))
      (node (ref "R441") (pin "1") (pinfunction "1_1") (pintype "passive"))
    )
    (net (code "62") (name "Net-(P411-Pad2)") (class "Default")
      (node (ref "P411") (pin "2") (pinfunction "2_2") (pintype "passive"))
      (node (ref "R439") (pin "1") (pinfunction "1_1") (pintype "passive"))
    )
    (net (code "63") (name "Net-(P412-Pad1)") (class "Default")
      (node (ref "P412") (pin "1") (pinfunction "1_1") (pintype "passive"))
      (node (ref "R445") (pin "1") (pinfunction "1_1") (pintype "passive"))
    )
    (net (code "64") (name "Net-(P412-Pad2)") (class "Default")
      (node (ref "P412") (pin "2") (pinfunction "2_2") (pintype "passive"))
      (node (ref "R443") (pin "1") (pinfunction "1_1") (pintype "passive"))
    )
    (net (code "65") (name "Net-(P413-Pad1)") (class "Default")
      (node (ref "P413") (pin "1") (pinfunction "1_1") (pintype "passive"))
      (node (ref "R449") (pin "1") (pinfunction "1_1") (pintype "passive"))
    )
    (net (code "66") (name "Net-(P413-Pad2)") (class "Default")
      (node (ref "P413") (pin "2") (pinfunction "2_2") (pintype "passive"))
      (node (ref "R447") (pin "1") (pinfunction "1_1") (pintype "passive"))
    )
    (net (code "67") (name "Net-(P414-Pad1)") (class "Default")
      (node (ref "P414") (pin "1") (pinfunction "1_1") (pintype "passive"))
      (node (ref "R453") (pin "1") (pinfunction "1_1") (pintype "passive"))
    )
    (net (code "68") (name "Net-(P414-Pad2)") (class "Default")
      (node (ref "P414") (pin "2") (pinfunction "2_2") (pintype "passive"))
      (node (ref "R451") (pin "1") (pinfunction "1_1") (pintype "passive"))
    )
    (net (code "69") (name "Net-(U400-A1)") (class "Default")
      (node (ref "R402") (pin "2") (pinfunction "2_2") (pintype "passive"))
      (node (ref "U400") (pin "2") (pinfunction "A1_2") (pintype "input"))
    )
    (net (code "70") (name "Net-(U400-A2)") (class "Default")
      (node (ref "R404") (pin "2") (pinfunction "2_2") (pintype "passive"))
      (node (ref "U400") (pin "4") (pinfunction "A2_4") (pintype "input"))
    )
    (net (code "71") (name "Net-(U400-A3)") (class "Default")
      (node (ref "R406") (pin "2") (pinfunction "2_2") (pintype "passive"))
      (node (ref "U400") (pin "6") (pinfunction "A3_6") (pintype "input"))
    )
    (net (code "72") (name "Net-(U400-A4)") (class "Default")
      (node (ref "R408") (pin "2") (pinfunction "2_2") (pintype "passive"))
      (node (ref "U400") (pin "8") (pinfunction "A4_8") (pintype "input"))
    )
    (net (code "73") (name "Net-(U400-A5)") (class "Default")
      (node (ref "R410") (pin "2") (pinfunction "2_2") (pintype "passive"))
      (node (ref "U400") (pin "11") (pinfunction "A5_11") (pintype "input"))
    )
    (net (code "74") (name "Net-(U400-A6)") (class "Default")
      (node (ref "R412") (pin "2") (pinfunction "2_2") (pintype "passive"))
      (node (ref "U400") (pin "13") (pinfunction "A6_13") (pintype "input"))
    )
    (net (code "75") (name "Net-(U400-A7)") (class "Default")
      (node (ref "R414") (pin "2") (pinfunction "2_2") (pintype "passive"))
      (node (ref "U400") (pin "15") (pinfunction "A7_15") (pintype "input"))
    )
    (net (code "76") (name "Net-(U400-A8)") (class "Default")
      (node (ref "R416") (pin "2") (pinfunction "2_2") (pintype "passive"))
      (node (ref "U400") (pin "17") (pinfunction "A8_17") (pintype "input"))
    )
    (net (code "77") (name "Net-(U401-A1)") (class "Default")
      (node (ref "R420") (pin "2") (pinfunction "2_2") (pintype "passive"))
      (node (ref "U401") (pin "2") (pinfunction "A1_2") (pintype "input"))
    )
    (net (code "78") (name "Net-(U401-A2)") (class "Default")
      (node (ref "R422") (pin "2") (pinfunction "2_2") (pintype "passive"))
      (node (ref "U401") (pin "4") (pinfunction "A2_4") (pintype "input"))
    )
    (net (code "79") (name "Net-(U401-A3)") (class "Default")
      (node (ref "R424") (pin "2") (pinfunction "2_2") (pintype "passive"))
      (node (ref "U401") (pin "6") (pinfunction "A3_6") (pintype "input"))
    )
    (net (code "80") (name "Net-(U401-A4)") (class "Default")
      (node (ref "R426") (pin "2") (pinfunction "2_2") (pintype "passive"))
      (node (ref "U401") (pin "8") (pinfunction "A4_8") (pintype "input"))
    )
    (net (code "81") (name "Net-(U401-A5)") (class "Default")
      (node (ref "R428") (pin "2") (pinfunction "2_2") (pintype "passive"))
      (node (ref "U401") (pin "11") (pinfunction "A5_11") (pintype "input"))
    )
    (net (code "82") (name "Net-(U401-A6)") (class "Default")
      (node (ref "R430") (pin "2") (pinfunction "2_2") (pintype "passive"))
      (node (ref "U401") (pin "13") (pinfunction "A6_13") (pintype "input"))
    )
    (net (code "83") (name "Net-(U401-A7)") (class "Default")
      (node (ref "R432") (pin "2") (pinfunction "2_2") (pintype "passive"))
      (node (ref "U401") (pin "15") (pinfunction "A7_15") (pintype "input"))
    )
    (net (code "84") (name "Net-(U401-A8)") (class "Default")
      (node (ref "R434") (pin "2") (pinfunction "2_2") (pintype "passive"))
      (node (ref "U401") (pin "17") (pinfunction "A8_17") (pintype "input"))
    )
    (net (code "85") (name "Net-(U402-A1)") (class "Default")
      (node (ref "R438") (pin "2") (pinfunction "2_2") (pintype "passive"))
      (node (ref "U402") (pin "2") (pinfunction "A1_2") (pintype "input"))
    )
    (net (code "86") (name "Net-(U402-A2)") (class "Default")
      (node (ref "R440") (pin "2") (pinfunction "2_2") (pintype "passive"))
      (node (ref "U402") (pin "4") (pinfunction "A2_4") (pintype "input"))
    )
    (net (code "87") (name "Net-(U402-A3)") (class "Default")
      (node (ref "R442") (pin "2") (pinfunction "2_2") (pintype "passive"))
      (node (ref "U402") (pin "6") (pinfunction "A3_6") (pintype "input"))
    )
    (net (code "88") (name "Net-(U402-A4)") (class "Default")
      (node (ref "R444") (pin "2") (pinfunction "2_2") (pintype "passive"))
      (node (ref "U402") (pin "8") (pinfunction "A4_8") (pintype "input"))
    )
    (net (code "89") (name "Net-(U402-A5)") (class "Default")
      (node (ref "R446") (pin "2") (pinfunction "2_2") (pintype "passive"))
      (node (ref "U402") (pin "11") (pinfunction "A5_11") (pintype "input"))
    )
    (net (code "90") (name "Net-(U402-A6)") (class "Default")
      (node (ref "R448") (pin "2") (pinfunction "2_2") (pintype "passive"))
      (node (ref "U402") (pin "13") (pinfunction "A6_13") (pintype "input"))
    )
    (net (code "91") (name "Net-(U402-A7)") (class "Default")
      (node (ref "R450") (pin "2") (pinfunction "2_2") (pintype "passive"))
      (node (ref "U402") (pin "15") (pinfunction "A7_15") (pintype "input"))
    )
    (net (code "92") (name "Net-(U402-A8)") (class "Default")
      (node (ref "R452") (pin "2") (pinfunction "2_2") (pintype "passive"))
      (node (ref "U402") (pin "17") (pinfunction "A8_17") (pintype "input"))
    )
    (net (code "93") (name "VSS") (class "Default")
      (node (ref "C400") (pin "1") (pinfunction "1_1") (pintype "passive"))
      (node (ref "C401") (pin "2") (pinfunction "2_2") (pintype "passive"))
      (node (ref "C402") (pin "2") (pinfunction "2_2") (pintype "passive"))
      (node (ref "C403") (pin "2") (pinfunction "2_2") (pintype "passive"))
      (node (ref "C404") (pin "2") (pinfunction "2_2") (pintype "passive"))
      (node (ref "C405") (pin "2") (pinfunction "2_2") (pintype "passive"))
      (node (ref "C406") (pin "2") (pinfunction "2_2") (pintype "passive"))
      (node (ref "C407") (pin "2") (pinfunction "2_2") (pintype "passive"))
      (node (ref "C408") (pin "2") (pinfunction "2_2") (pintype "passive"))
      (node (ref "C409") (pin "2") (pinfunction "2_2") (pintype "passive"))
      (node (ref "C410") (pin "1") (pinfunction "1_1") (pintype "passive"))
      (node (ref "C411") (pin "2") (pinfunction "2_2") (pintype "passive"))
      (node (ref "C412") (pin "2") (pinfunction "2_2") (pintype "passive"))
      (node (ref "C413") (pin "2") (pinfunction "2_2") (pintype "passive"))
      (node (ref "C414") (pin "2") (pinfunction "2_2") (pintype "passive"))
      (node (ref "C415") (pin "2") (pinfunction "2_2") (pintype "passive"))
      (node (ref "C416") (pin "2") (pinfunction "2_2") (pintype "passive"))
      (node (ref "C417") (pin "2") (pinfunction "2_2") (pintype "passive"))
      (node (ref "C418") (pin "2") (pinfunction "2_2") (pintype "passive"))
      (node (ref "C419") (pin "2") (pinfunction "2_2") (pintype "passive"))
      (node (ref "C420") (pin "1") (pinfunction "1_1") (pintype "passive"))
      (node (ref "C421") (pin "2") (pinfunction "2_2") (pintype "passive"))
      (node (ref "C422") (pin "2") (pinfunction "2_2") (pintype "passive"))
      (node (ref "C423") (pin "2") (pinfunction "2_2") (pintype "passive"))
      (node (ref "C424") (pin "2") (pinfunction "2_2") (pintype "passive"))
      (node (ref "C425") (pin "2") (pinfunction "2_2") (pintype "passive"))
      (node (ref "C426") (pin "2") (pinfunction "2_2") (pintype "passive"))
      (node (ref "C427") (pin "2") (pinfunction "2_2") (pintype "passive"))
      (node (ref "C428") (pin "2") (pinfunction "2_2") (pintype "passive"))
      (node (ref "C429") (pin "2") (pinfunction "2_2") (pintype "passive"))
      (node (ref "D400") (pin "1") (pinfunction "A_1") (pintype "passive"))
      (node (ref "D401") (pin "1") (pinfunction "A_1") (pintype "passive"))
      (node (ref "D402") (pin "1") (pinfunction "A_1") (pintype "passive"))
      (node (ref "D403") (pin "1") (pinfunction "A_1") (pintype "passive"))
      (node (ref "D404") (pin "1") (pinfunction "A_1") (pintype "passive"))
      (node (ref "D405") (pin "1") (pinfunction "A_1") (pintype "passive"))
      (node (ref "D406") (pin "1") (pinfunction "A_1") (pintype "passive"))
      (node (ref "D407") (pin "1") (pinfunction "A_1") (pintype "passive"))
      (node (ref "D408") (pin "1") (pinfunction "A_1") (pintype "passive"))
      (node (ref "D409") (pin "1") (pinfunction "A_1") (pintype "passive"))
      (node (ref "D410") (pin "1") (pinfunction "A_1") (pintype "passive"))
      (node (ref "D411") (pin "1") (pinfunction "A_1") (pintype "passive"))
      (node (ref "D412") (pin "1") (pinfunction "A_1") (pintype "passive"))
      (node (ref "D413") (pin "1") (pinfunction "A_1") (pintype "passive"))
      (node (ref "D414") (pin "1") (pinfunction "A_1") (pintype "passive"))
      (node (ref "D415") (pin "1") (pinfunction "A_1") (pintype "passive"))
      (node (ref "D416") (pin "1") (pinfunction "A_1") (pintype "passive"))
      (node (ref "D417") (pin "1") (pinfunction "A_1") (pintype "passive"))
      (node (ref "D418") (pin "1") (pinfunction "A_1") (pintype "passive"))
      (node (ref "D419") (pin "1") (pinfunction "A_1") (pintype "passive"))
      (node (ref "D420") (pin "1") (pinfunction "A_1") (pintype "passive"))
      (node (ref "D421") (pin "1") (pinfunction "A_1") (pintype "passive"))
      (node (ref "D422") (pin "1") (pinfunction "A_1") (pintype "passive"))
      (node (ref "D423") (pin "1") (pinfunction "A_1") (pintype "passive"))
      (node (ref "P415") (pin "11") (pinfunction "11_11") (pintype "passive"))
      (node (ref "R417") (pin "2") (pinfunction "2_2") (pintype "passive"))
      (node (ref "R435") (pin "2") (pinfunction "2_2") (pintype "passive"))
      (node (ref "R453") (pin "2") (pinfunction "2_2") (pintype "passive"))
      (node (ref "U400") (pin "10") (pinfunction "GND_10") (pintype "power_in"))
      (node (ref "U401") (pin "10") (pinfunction "GND_10") (pintype "power_in"))
      (node (ref "U402") (pin "10") (pinfunction "GND_10") (pintype "power_in"))
    )
  )
)
